# B360D.net
KiCad netlist of a schematic drawn in EAGLE
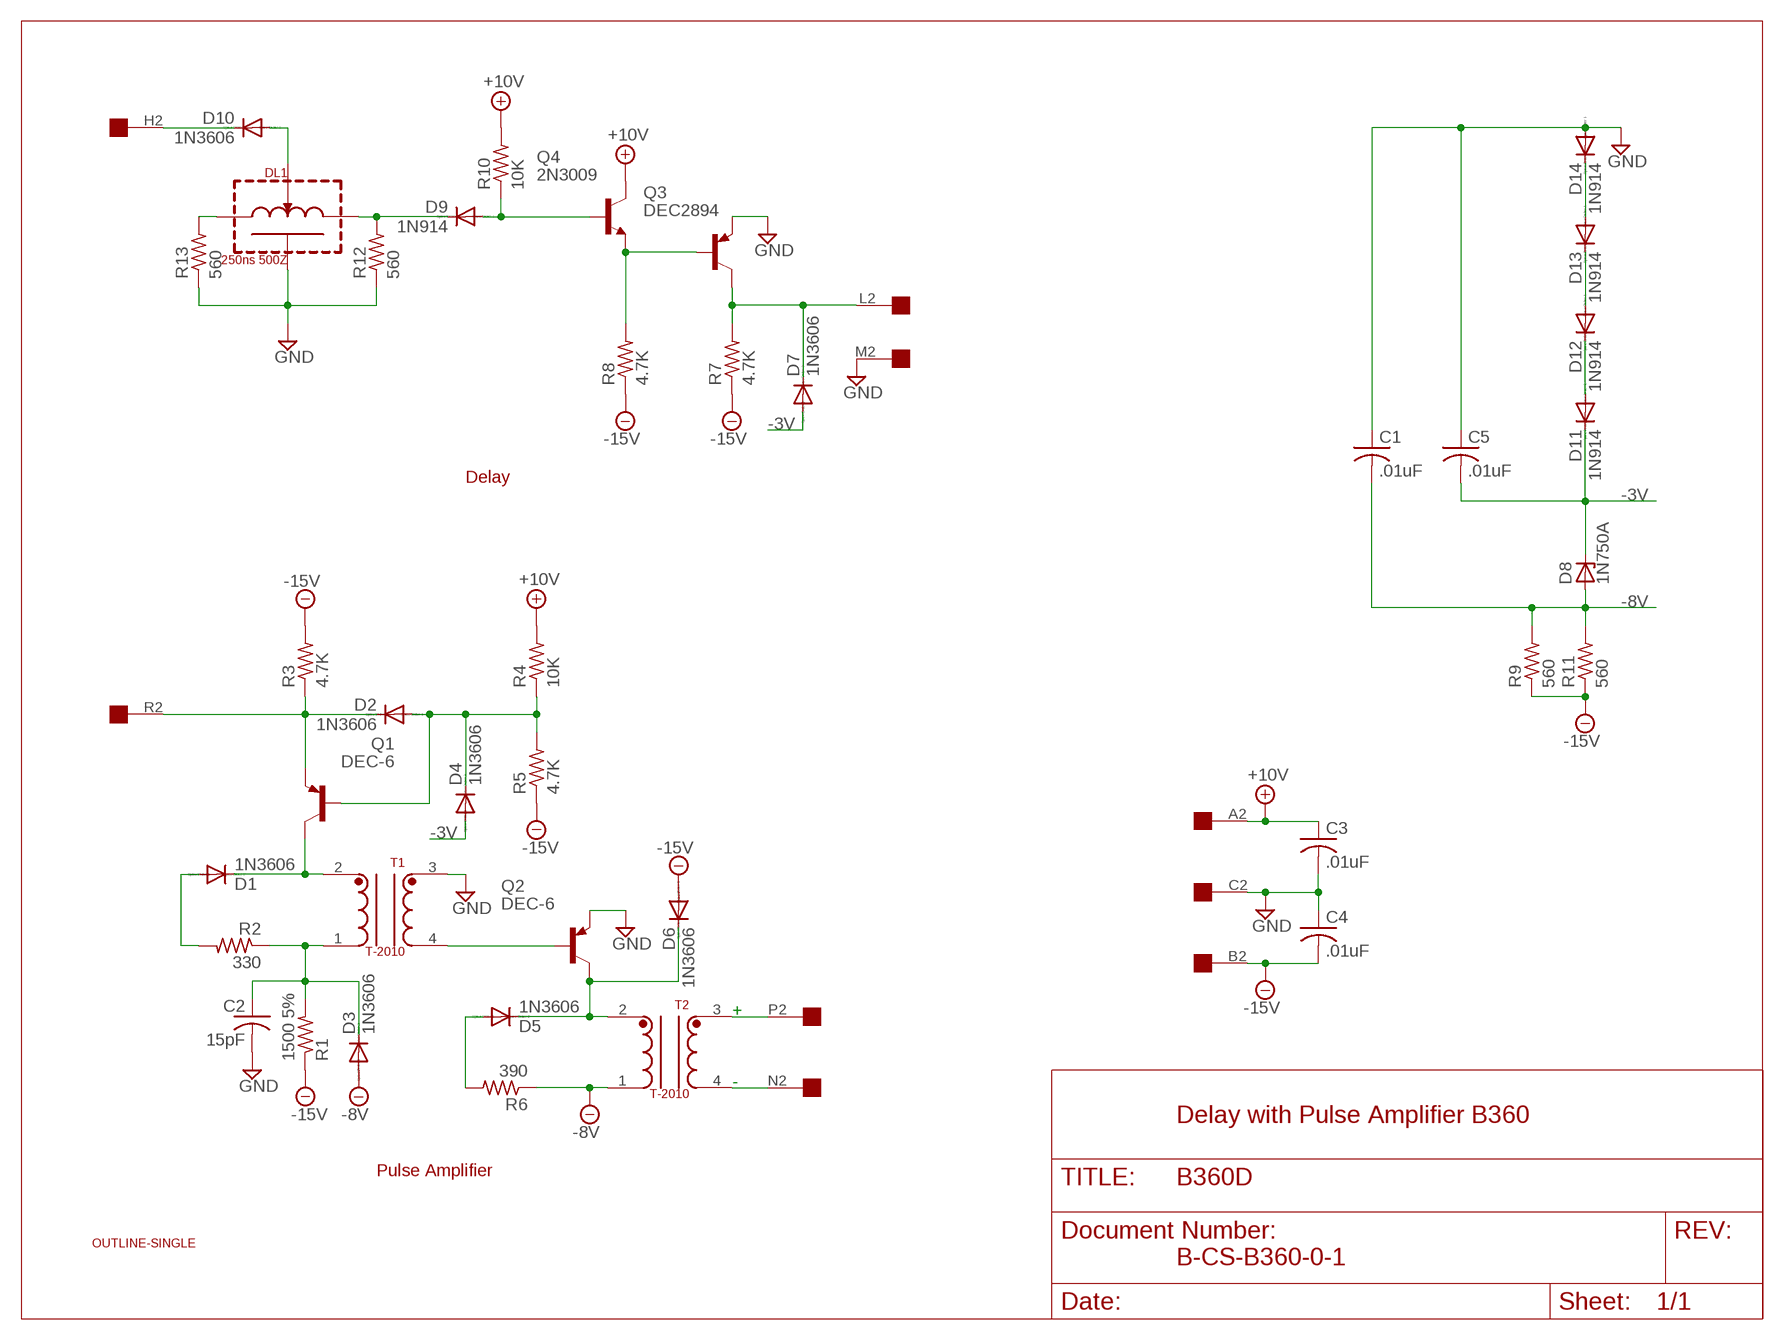
[diagram p0: schematic, sheet 1]

(export (version "E")
  (design (tool "Eeschema 10.0.6"))
  (components
    (comp (ref "C1")
      (value ".01uF")
      (footprint "eagle-import:C050-025X075")
      (libsource (lib "eagle-import") (part "C-US050-025X075"))
    )
    (comp (ref "C2")
      (value "15pF")
      (footprint "eagle-import:C050-025X075")
      (libsource (lib "eagle-import") (part "C-US050-025X075"))
    )
    (comp (ref "C3")
      (value ".01uF")
      (footprint "eagle-import:C050-025X075")
      (libsource (lib "eagle-import") (part "C-US050-025X075"))
    )
    (comp (ref "C4")
      (value ".01uF")
      (footprint "eagle-import:C050-025X075")
      (libsource (lib "eagle-import") (part "C-US050-025X075"))
    )
    (comp (ref "C5")
      (value ".01uF")
      (footprint "eagle-import:C050-025X075")
      (libsource (lib "eagle-import") (part "C-US050-025X075"))
    )
    (comp (ref "D1")
      (value "1N3606")
      (footprint "eagle-import:DO35-10")
      (libsource (lib "eagle-import") (part "1N4148DO35-10"))
    )
    (comp (ref "D2")
      (value "1N3606")
      (footprint "eagle-import:DO35-10")
      (libsource (lib "eagle-import") (part "1N4148DO35-10"))
    )
    (comp (ref "D3")
      (value "1N3606")
      (footprint "eagle-import:DO35-10")
      (libsource (lib "eagle-import") (part "1N4148DO35-10"))
    )
    (comp (ref "D4")
      (value "1N3606")
      (footprint "eagle-import:DO35-10")
      (libsource (lib "eagle-import") (part "1N4148DO35-10"))
    )
    (comp (ref "D5")
      (value "1N3606")
      (footprint "eagle-import:DO35-10")
      (libsource (lib "eagle-import") (part "1N4148DO35-10"))
    )
    (comp (ref "D6")
      (value "1N3606")
      (footprint "eagle-import:DO35-10")
      (libsource (lib "eagle-import") (part "1N4148DO35-10"))
    )
    (comp (ref "D7")
      (value "1N3606")
      (footprint "eagle-import:DO35-10")
      (libsource (lib "eagle-import") (part "1N4148DO35-10"))
    )
    (comp (ref "D8")
      (value "1N750A")
      (footprint "eagle-import:DO35Z10")
      (libsource (lib "eagle-import") (part "ZENER-DIODEDO35Z10"))
    )
    (comp (ref "D9")
      (value "1N914")
      (footprint "eagle-import:DO35-10")
      (libsource (lib "eagle-import") (part "1N4148DO35-10"))
    )
    (comp (ref "D10")
      (value "1N3606")
      (footprint "eagle-import:DO35-10")
      (libsource (lib "eagle-import") (part "1N4148DO35-10"))
    )
    (comp (ref "D11")
      (value "1N914")
      (footprint "eagle-import:DO35-10")
      (libsource (lib "eagle-import") (part "1N4148DO35-10"))
    )
    (comp (ref "D12")
      (value "1N914")
      (footprint "eagle-import:DO35-10")
      (libsource (lib "eagle-import") (part "1N4148DO35-10"))
    )
    (comp (ref "D13")
      (value "1N914")
      (footprint "eagle-import:DO35-10")
      (libsource (lib "eagle-import") (part "1N4148DO35-10"))
    )
    (comp (ref "D14")
      (value "1N914")
      (footprint "eagle-import:DO35-10")
      (libsource (lib "eagle-import") (part "1N4148DO35-10"))
    )
    (comp (ref "DL1")
      (value "250ns 500Z")
      (footprint "eagle-import:DELAYLINE")
      (libsource (lib "eagle-import") (part "DELAYLINE"))
    )
    (comp (ref "Q1")
      (value "DEC-6")
      (footprint "eagle-import:TO39")
      (libsource (lib "eagle-import") (part "2N2904"))
    )
    (comp (ref "Q2")
      (value "DEC-6")
      (footprint "eagle-import:TO39")
      (libsource (lib "eagle-import") (part "2N2904"))
    )
    (comp (ref "Q3")
      (value "DEC2894")
      (footprint "eagle-import:TO39")
      (libsource (lib "eagle-import") (part "2N2904"))
    )
    (comp (ref "Q4")
      (value "2N3009")
      (footprint "eagle-import:TO39")
      (libsource (lib "eagle-import") (part "-NPN-TO39-EBC2N2102"))
    )
    (comp (ref "R1")
      (value "1500 5%")
      (footprint "eagle-import:0207_10")
      (libsource (lib "eagle-import") (part "R-US_0207/10"))
    )
    (comp (ref "R2")
      (value "330")
      (footprint "eagle-import:0207_10")
      (libsource (lib "eagle-import") (part "R-US_0207/10"))
    )
    (comp (ref "R3")
      (value "4.7K")
      (footprint "eagle-import:0207_10")
      (libsource (lib "eagle-import") (part "R-US_0207/10"))
    )
    (comp (ref "R4")
      (value "10K")
      (footprint "eagle-import:0207_10")
      (libsource (lib "eagle-import") (part "R-US_0207/10"))
    )
    (comp (ref "R5")
      (value "4.7K")
      (footprint "eagle-import:0207_10")
      (libsource (lib "eagle-import") (part "R-US_0207/10"))
    )
    (comp (ref "R6")
      (value "390")
      (footprint "eagle-import:0207_10")
      (libsource (lib "eagle-import") (part "R-US_0207/10"))
    )
    (comp (ref "R7")
      (value "4.7K")
      (footprint "eagle-import:0207_10")
      (libsource (lib "eagle-import") (part "R-US_0207/10"))
    )
    (comp (ref "R8")
      (value "4.7K")
      (footprint "eagle-import:0207_10")
      (libsource (lib "eagle-import") (part "R-US_0207/10"))
    )
    (comp (ref "R9")
      (value "560")
      (footprint "eagle-import:0207_10")
      (libsource (lib "eagle-import") (part "R-US_0207/10"))
    )
    (comp (ref "R10")
      (value "10K")
      (footprint "eagle-import:0207_10")
      (libsource (lib "eagle-import") (part "R-US_0207/10"))
    )
    (comp (ref "R11")
      (value "560")
      (footprint "eagle-import:0207_10")
      (libsource (lib "eagle-import") (part "R-US_0207/10"))
    )
    (comp (ref "R12")
      (value "560")
      (footprint "eagle-import:0207_10")
      (libsource (lib "eagle-import") (part "R-US_0207/10"))
    )
    (comp (ref "R13")
      (value "560")
      (footprint "eagle-import:0207_10")
      (libsource (lib "eagle-import") (part "R-US_0207/10"))
    )
    (comp (ref "T1")
      (value "T-2010")
      (footprint "eagle-import:TRANSFORMER2")
      (libsource (lib "eagle-import") (part "T-2010"))
    )
    (comp (ref "T2")
      (value "T-2010")
      (footprint "eagle-import:TRANSFORMER2")
      (libsource (lib "eagle-import") (part "T-2010"))
    )
    (comp (ref "U$1")
      (value "OUTLINE-SINGLE")
      (footprint "eagle-import:SINGLE")
      (libsource (lib "eagle-import") (part "OUTLINE-SINGLE"))
    )
    (comp (ref "U$2")
      (value "EDGE-1")
      (footprint "eagle-import:EDGE-CON1")
      (libsource (lib "eagle-import") (part "EDGE-1"))
    )
  )
  (nets
    (net (code "1") (name "+10V") (class "Default")
      (node (ref "C3") (pin "1") (pinfunction "1_1") (pintype "passive"))
      (node (ref "Q4") (pin "3") (pinfunction "C_3") (pintype "passive"))
      (node (ref "R10") (pin "2") (pinfunction "2_2") (pintype "passive"))
      (node (ref "R4") (pin "2") (pinfunction "2_2") (pintype "passive"))
      (node (ref "U$2") (pin "A2") (pinfunction "1_A2") (pintype "bidirectional"))
    )
    (net (code "2") (name "-8V") (class "Default")
      (node (ref "C1") (pin "2") (pinfunction "2_2") (pintype "passive"))
      (node (ref "D3") (pin "A") (pinfunction "A_A") (pintype "passive"))
      (node (ref "D8") (pin "A") (pinfunction "A_A") (pintype "passive"))
      (node (ref "R11") (pin "2") (pinfunction "2_2") (pintype "passive"))
      (node (ref "R6") (pin "1") (pinfunction "1_1") (pintype "passive"))
      (node (ref "R9") (pin "2") (pinfunction "2_2") (pintype "passive"))
      (node (ref "T2") (pin "1") (pinfunction "P$5_1") (pintype "passive"))
    )
    (net (code "3") (name "-15V") (class "Default")
      (node (ref "C4") (pin "2") (pinfunction "2_2") (pintype "passive"))
      (node (ref "D6") (pin "A") (pinfunction "A_A") (pintype "passive"))
      (node (ref "R1") (pin "1") (pinfunction "1_1") (pintype "passive"))
      (node (ref "R11") (pin "1") (pinfunction "1_1") (pintype "passive"))
      (node (ref "R3") (pin "2") (pinfunction "2_2") (pintype "passive"))
      (node (ref "R5") (pin "1") (pinfunction "1_1") (pintype "passive"))
      (node (ref "R7") (pin "1") (pinfunction "1_1") (pintype "passive"))
      (node (ref "R8") (pin "1") (pinfunction "1_1") (pintype "passive"))
      (node (ref "R9") (pin "1") (pinfunction "1_1") (pintype "passive"))
      (node (ref "U$2") (pin "B2") (pinfunction "1_B2") (pintype "bidirectional"))
    )
    (net (code "4") (name "/-3V") (class "Default")
      (node (ref "C5") (pin "2") (pinfunction "2_2") (pintype "passive"))
      (node (ref "D11") (pin "C") (pinfunction "C_C") (pintype "passive"))
      (node (ref "D4") (pin "A") (pinfunction "A_A") (pintype "passive"))
      (node (ref "D7") (pin "A") (pinfunction "A_A") (pintype "passive"))
      (node (ref "D8") (pin "C") (pinfunction "C_C") (pintype "passive"))
    )
    (net (code "5") (name "GND") (class "Default")
      (node (ref "C1") (pin "1") (pinfunction "1_1") (pintype "passive"))
      (node (ref "C2") (pin "2") (pinfunction "2_2") (pintype "passive"))
      (node (ref "C3") (pin "2") (pinfunction "2_2") (pintype "passive"))
      (node (ref "C4") (pin "1") (pinfunction "1_1") (pintype "passive"))
      (node (ref "C5") (pin "1") (pinfunction "1_1") (pintype "passive"))
      (node (ref "D14") (pin "A") (pinfunction "A_A") (pintype "passive"))
      (node (ref "DL1") (pin "G") (pinfunction "G_G") (pintype "passive"))
      (node (ref "Q2") (pin "1") (pinfunction "E_1") (pintype "passive"))
      (node (ref "Q3") (pin "1") (pinfunction "E_1") (pintype "passive"))
      (node (ref "R12") (pin "1") (pinfunction "1_1") (pintype "passive"))
      (node (ref "R13") (pin "1") (pinfunction "1_1") (pintype "passive"))
      (node (ref "T1") (pin "3") (pinfunction "P$2_3") (pintype "passive"))
      (node (ref "U$2") (pin "C2") (pinfunction "1_C2") (pintype "bidirectional"))
      (node (ref "U$2") (pin "M2") (pinfunction "1_M2") (pintype "bidirectional"))
    )
    (net (code "6") (name "Net-(D1-PadA)") (class "Default")
      (node (ref "D1") (pin "A") (pinfunction "A_A") (pintype "passive"))
      (node (ref "R2") (pin "2") (pinfunction "2_2") (pintype "passive"))
    )
    (net (code "7") (name "Net-(D5-PadA)") (class "Default")
      (node (ref "D5") (pin "A") (pinfunction "A_A") (pintype "passive"))
      (node (ref "R6") (pin "2") (pinfunction "2_2") (pintype "passive"))
    )
    (net (code "8") (name "Net-(D9-PadC)") (class "Default")
      (node (ref "D9") (pin "C") (pinfunction "C_C") (pintype "passive"))
      (node (ref "DL1") (pin "L") (pinfunction "L_L") (pintype "passive"))
      (node (ref "R12") (pin "2") (pinfunction "2_2") (pintype "passive"))
    )
    (net (code "9") (name "Net-(D10-PadA)") (class "Default")
      (node (ref "D10") (pin "A") (pinfunction "A_A") (pintype "passive"))
      (node (ref "DL1") (pin "V") (pinfunction "V_V") (pintype "passive"))
    )
    (net (code "10") (name "Net-(D11-PadA)") (class "Default")
      (node (ref "D11") (pin "A") (pinfunction "A_A") (pintype "passive"))
      (node (ref "D12") (pin "C") (pinfunction "C_C") (pintype "passive"))
    )
    (net (code "11") (name "Net-(D12-PadA)") (class "Default")
      (node (ref "D12") (pin "A") (pinfunction "A_A") (pintype "passive"))
      (node (ref "D13") (pin "C") (pinfunction "C_C") (pintype "passive"))
    )
    (net (code "12") (name "Net-(D13-PadA)") (class "Default")
      (node (ref "D13") (pin "A") (pinfunction "A_A") (pintype "passive"))
      (node (ref "D14") (pin "C") (pinfunction "C_C") (pintype "passive"))
    )
    (net (code "13") (name "Net-(DL1-PadR)") (class "Default")
      (node (ref "DL1") (pin "R") (pinfunction "R_R") (pintype "passive"))
      (node (ref "R13") (pin "2") (pinfunction "2_2") (pintype "passive"))
    )
    (net (code "14") (name "Net-(Q1-B)") (class "Default")
      (node (ref "D2") (pin "A") (pinfunction "A_A") (pintype "passive"))
      (node (ref "D4") (pin "C") (pinfunction "C_C") (pintype "passive"))
      (node (ref "Q1") (pin "2") (pinfunction "B_2") (pintype "passive"))
      (node (ref "R4") (pin "1") (pinfunction "1_1") (pintype "passive"))
      (node (ref "R5") (pin "2") (pinfunction "2_2") (pintype "passive"))
    )
    (net (code "15") (name "Net-(Q1-C)") (class "Default")
      (node (ref "D1") (pin "C") (pinfunction "C_C") (pintype "passive"))
      (node (ref "Q1") (pin "3") (pinfunction "C_3") (pintype "passive"))
      (node (ref "T1") (pin "2") (pinfunction "P$4_2") (pintype "passive"))
    )
    (net (code "16") (name "Net-(Q1-E)") (class "Default")
      (node (ref "D2") (pin "C") (pinfunction "C_C") (pintype "passive"))
      (node (ref "Q1") (pin "1") (pinfunction "E_1") (pintype "passive"))
      (node (ref "R3") (pin "1") (pinfunction "1_1") (pintype "passive"))
      (node (ref "U$2") (pin "R2") (pinfunction "1_R2") (pintype "bidirectional"))
    )
    (net (code "17") (name "Net-(Q2-B)") (class "Default")
      (node (ref "Q2") (pin "2") (pinfunction "B_2") (pintype "passive"))
      (node (ref "T1") (pin "4") (pinfunction "P$7_4") (pintype "passive"))
    )
    (net (code "18") (name "Net-(Q2-C)") (class "Default")
      (node (ref "D5") (pin "C") (pinfunction "C_C") (pintype "passive"))
      (node (ref "D6") (pin "C") (pinfunction "C_C") (pintype "passive"))
      (node (ref "Q2") (pin "3") (pinfunction "C_3") (pintype "passive"))
      (node (ref "T2") (pin "2") (pinfunction "P$4_2") (pintype "passive"))
    )
    (net (code "19") (name "Net-(Q3-B)") (class "Default")
      (node (ref "Q3") (pin "2") (pinfunction "B_2") (pintype "passive"))
      (node (ref "Q4") (pin "1") (pinfunction "E_1") (pintype "passive"))
      (node (ref "R8") (pin "2") (pinfunction "2_2") (pintype "passive"))
    )
    (net (code "20") (name "Net-(Q3-C)") (class "Default")
      (node (ref "D7") (pin "C") (pinfunction "C_C") (pintype "passive"))
      (node (ref "Q3") (pin "3") (pinfunction "C_3") (pintype "passive"))
      (node (ref "R7") (pin "2") (pinfunction "2_2") (pintype "passive"))
      (node (ref "U$2") (pin "L2") (pinfunction "1_L2") (pintype "bidirectional"))
    )
    (net (code "21") (name "Net-(Q4-B)") (class "Default")
      (node (ref "D9") (pin "A") (pinfunction "A_A") (pintype "passive"))
      (node (ref "Q4") (pin "2") (pinfunction "B_2") (pintype "passive"))
      (node (ref "R10") (pin "1") (pinfunction "1_1") (pintype "passive"))
    )
    (net (code "22") (name "Net-(T1-P$5)") (class "Default")
      (node (ref "C2") (pin "1") (pinfunction "1_1") (pintype "passive"))
      (node (ref "D3") (pin "C") (pinfunction "C_C") (pintype "passive"))
      (node (ref "R1") (pin "2") (pinfunction "2_2") (pintype "passive"))
      (node (ref "R2") (pin "1") (pinfunction "1_1") (pintype "passive"))
      (node (ref "T1") (pin "1") (pinfunction "P$5_1") (pintype "passive"))
    )
    (net (code "23") (name "Net-(T2-P$2)") (class "Default")
      (node (ref "T2") (pin "3") (pinfunction "P$2_3") (pintype "passive"))
      (node (ref "U$2") (pin "P2") (pinfunction "1_P2") (pintype "bidirectional"))
    )
    (net (code "24") (name "Net-(T2-P$7)") (class "Default")
      (node (ref "T2") (pin "4") (pinfunction "P$7_4") (pintype "passive"))
      (node (ref "U$2") (pin "N2") (pinfunction "1_N2") (pintype "bidirectional"))
    )
    (net (code "25") (name "Net-(U$2G-1)") (class "Default")
      (node (ref "D10") (pin "C") (pinfunction "C_C") (pintype "passive"))
      (node (ref "U$2") (pin "H2") (pinfunction "1_H2") (pintype "bidirectional"))
    )
  )
)
